# CAN_BUS.net
KiCad netlist of a schematic drawn in Altium Designer
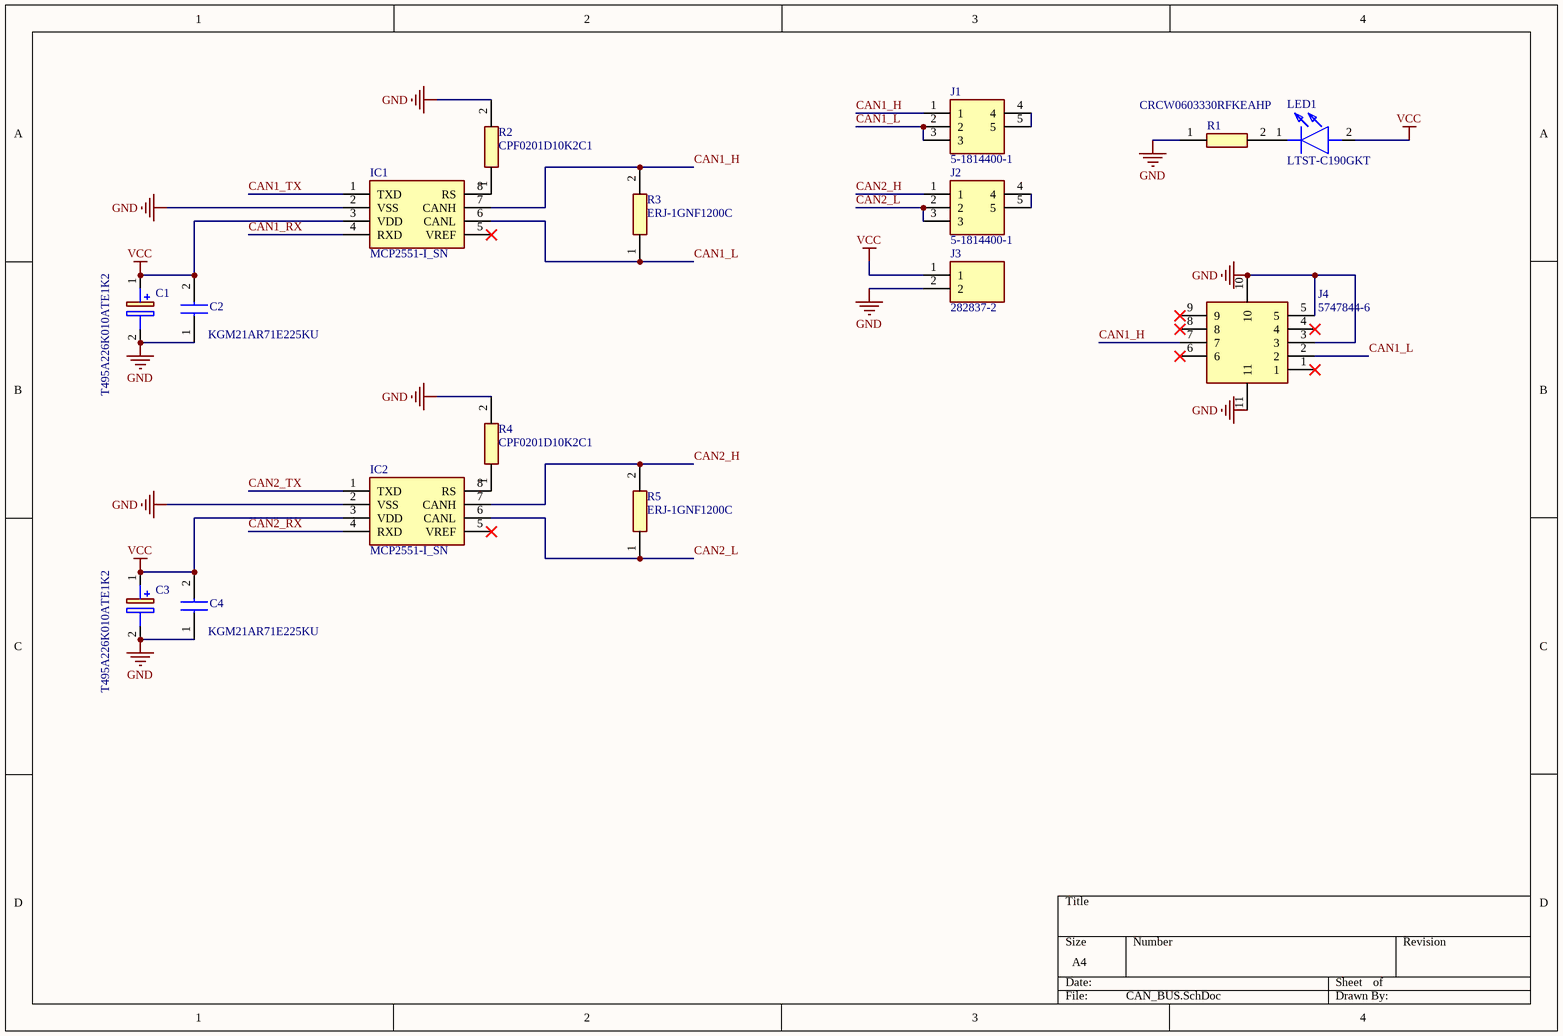
[diagram p0: CAN_BUS.SchDoc]

(export (version "E")
  (design (tool "Eeschema 10.0.6"))
  (components
    (comp (ref "C1")
      (value "T495A226K010ATE1K2")
      (footprint "CAN_BUS:T495A")
      (description "Capacitor Polarised")
      (fields (field (name "MOUSER PART NUMBER") "80-T495A226K10ATE1K2"))
      (libsource (lib "*") (part "T495A226K010ATE1K2"))
    )
    (comp (ref "C2")
      (value "KGM21AR71E225KU")
      (footprint "CAN_BUS:CAPC2012X135N")
      (description "Capacitor")
      (fields (field (name "MOUSER PART NUMBER") "581-KGM21AR71E225KU"))
      (libsource (lib "*") (part "KGM21AR71E225KU"))
    )
    (comp (ref "C3")
      (value "T495A226K010ATE1K2")
      (footprint "CAN_BUS:T495A")
      (description "Capacitor Polarised")
      (fields (field (name "MOUSER PART NUMBER") "80-T495A226K10ATE1K2"))
      (libsource (lib "*") (part "T495A226K010ATE1K2"))
    )
    (comp (ref "C4")
      (value "KGM21AR71E225KU")
      (footprint "CAN_BUS:CAPC2012X135N")
      (description "Capacitor")
      (fields (field (name "MOUSER PART NUMBER") "581-KGM21AR71E225KU"))
      (libsource (lib "*") (part "KGM21AR71E225KU"))
    )
    (comp (ref "IC1")
      (value "MCP2551-I_SN")
      (footprint "OptoIso:SOIC127P600X175-8N")
      (description "Integrated Circuit")
      (fields
        (field (name "MANUFACTURER_PART_NUMBER") "MCP2551-I/SN")
        (field (name "MOUSER PART NUMBER") "579-MCP2551-I/SN")
      )
      (libsource (lib "*") (part "MCP2551-I_SN"))
    )
    (comp (ref "IC2")
      (value "MCP2551-I_SN")
      (footprint "OptoIso:SOIC127P600X175-8N")
      (description "Integrated Circuit")
      (fields
        (field (name "MANUFACTURER_PART_NUMBER") "MCP2551-I/SN")
        (field (name "MOUSER PART NUMBER") "579-MCP2551-I/SN")
      )
      (libsource (lib "*") (part "MCP2551-I_SN"))
    )
    (comp (ref "J1")
      (value "5-1814400-1")
      (footprint "CAN_BUS:518144001")
      (description "Connector")
      (fields (field (name "MOUSER PART NUMBER") "571-5-1814400-1"))
      (libsource (lib "*") (part "5-1814400-1"))
    )
    (comp (ref "J2")
      (value "5-1814400-1")
      (footprint "CAN_BUS:518144001")
      (description "Connector")
      (fields (field (name "MOUSER PART NUMBER") "571-5-1814400-1"))
      (libsource (lib "*") (part "5-1814400-1"))
    )
    (comp (ref "J3")
      (value "282837-2")
      (footprint "CAN_BUS:2828372")
      (description "Connector")
      (fields (field (name "MOUSER PART NUMBER") "571-2828372"))
      (libsource (lib "*") (part "282837-2"))
    )
    (comp (ref "J4")
      (value "5747844-6")
      (footprint "CAN_BUS:57478446")
      (description "Connector")
      (fields (field (name "MOUSER PART NUMBER") "571-5747844-6"))
      (libsource (lib "*") (part "5747844-6"))
    )
    (comp (ref "LED1")
      (value "LTST-C190GKT")
      (footprint "CAN_BUS:LEDC1608X90N")
      (description "LED")
      (fields (field (name "MOUSER PART NUMBER") "859-LTST-C190GKT"))
      (libsource (lib "*") (part "LTST-C190GKT"))
    )
    (comp (ref "R1")
      (value "CRCW0603330RFKEAHP")
      (footprint "CAN_BUS:CAPC1608X55N")
      (description "Resistor")
      (fields (field (name "MOUSER PART NUMBER") "71-CRCW0603330RFKEAH"))
      (libsource (lib "*") (part "CRCW0603330RFKEAHP"))
    )
    (comp (ref "R2")
      (value "CPF0201D10K2C1")
      (footprint "OptoIso:RESC0603X28N")
      (description "Resistor")
      (libsource (lib "*") (part "CPF0201D10K2C1"))
    )
    (comp (ref "R3")
      (value "ERJ-1GNF1200C")
      (footprint "CAN_BUS:ERJ1GN_(0201)")
      (description "Resistor")
      (fields (field (name "MOUSER PART NUMBER") "667-ERJ-1GNF1200C"))
      (libsource (lib "*") (part "ERJ-1GNF1200C"))
    )
    (comp (ref "R4")
      (value "CPF0201D10K2C1")
      (footprint "OptoIso:RESC0603X28N")
      (description "Resistor")
      (libsource (lib "*") (part "CPF0201D10K2C1"))
    )
    (comp (ref "R5")
      (value "ERJ-1GNF1200C")
      (footprint "CAN_BUS:ERJ1GN_(0201)")
      (description "Resistor")
      (fields (field (name "MOUSER PART NUMBER") "667-ERJ-1GNF1200C"))
      (libsource (lib "*") (part "ERJ-1GNF1200C"))
    )
  )
  (nets
    (net (code "1") (name "/CAN1_H") (class "Default")
      (node (ref "IC1") (pin "7") (pinfunction "CANH_7") (pintype "passive"))
      (node (ref "J1") (pin "1") (pinfunction "1_1") (pintype "passive"))
      (node (ref "J4") (pin "7") (pinfunction "7_7") (pintype "passive"))
      (node (ref "R3") (pin "2") (pinfunction "2_2") (pintype "passive"))
    )
    (net (code "2") (name "/CAN1_L") (class "Default")
      (node (ref "IC1") (pin "6") (pinfunction "CANL_6") (pintype "passive"))
      (node (ref "J1") (pin "2") (pinfunction "2_2") (pintype "passive"))
      (node (ref "J1") (pin "3") (pinfunction "3_3") (pintype "passive"))
      (node (ref "J4") (pin "2") (pinfunction "2_2") (pintype "passive"))
      (node (ref "R3") (pin "1") (pinfunction "1_1") (pintype "passive"))
    )
    (net (code "3") (name "/CAN1_RX") (class "Default")
      (node (ref "IC1") (pin "4") (pinfunction "RXD_4") (pintype "passive"))
    )
    (net (code "4") (name "/CAN1_TX") (class "Default")
      (node (ref "IC1") (pin "1") (pinfunction "TXD_1") (pintype "passive"))
    )
    (net (code "5") (name "/CAN2_H") (class "Default")
      (node (ref "IC2") (pin "7") (pinfunction "CANH_7") (pintype "passive"))
      (node (ref "J2") (pin "1") (pinfunction "1_1") (pintype "passive"))
      (node (ref "R5") (pin "2") (pinfunction "2_2") (pintype "passive"))
    )
    (net (code "6") (name "/CAN2_L") (class "Default")
      (node (ref "IC2") (pin "6") (pinfunction "CANL_6") (pintype "passive"))
      (node (ref "J2") (pin "2") (pinfunction "2_2") (pintype "passive"))
      (node (ref "J2") (pin "3") (pinfunction "3_3") (pintype "passive"))
      (node (ref "R5") (pin "1") (pinfunction "1_1") (pintype "passive"))
    )
    (net (code "7") (name "/CAN2_RX") (class "Default")
      (node (ref "IC2") (pin "4") (pinfunction "RXD_4") (pintype "passive"))
    )
    (net (code "8") (name "/CAN2_TX") (class "Default")
      (node (ref "IC2") (pin "1") (pinfunction "TXD_1") (pintype "passive"))
    )
    (net (code "9") (name "GND") (class "Default")
      (node (ref "C1") (pin "2") (pinfunction "-_2") (pintype "passive"))
      (node (ref "C2") (pin "1") (pinfunction "1_1") (pintype "passive"))
      (node (ref "C3") (pin "2") (pinfunction "-_2") (pintype "passive"))
      (node (ref "C4") (pin "1") (pinfunction "1_1") (pintype "passive"))
      (node (ref "IC1") (pin "2") (pinfunction "VSS_2") (pintype "passive"))
      (node (ref "IC2") (pin "2") (pinfunction "VSS_2") (pintype "passive"))
      (node (ref "J3") (pin "2") (pinfunction "2_2") (pintype "passive"))
      (node (ref "J4") (pin "10") (pinfunction "10_10") (pintype "passive"))
      (node (ref "J4") (pin "11") (pinfunction "11_11") (pintype "passive"))
      (node (ref "J4") (pin "3") (pinfunction "3_3") (pintype "passive"))
      (node (ref "J4") (pin "5") (pinfunction "5_5") (pintype "passive"))
      (node (ref "R1") (pin "1") (pinfunction "1_1") (pintype "passive"))
      (node (ref "R2") (pin "2") (pinfunction "2_2") (pintype "passive"))
      (node (ref "R4") (pin "2") (pinfunction "2_2") (pintype "passive"))
    )
    (net (code "10") (name "Net-(IC1-RS)") (class "Default")
      (node (ref "IC1") (pin "8") (pinfunction "RS_8") (pintype "passive"))
      (node (ref "R2") (pin "1") (pinfunction "1_1") (pintype "passive"))
    )
    (net (code "11") (name "Net-(IC2-RS)") (class "Default")
      (node (ref "IC2") (pin "8") (pinfunction "RS_8") (pintype "passive"))
      (node (ref "R4") (pin "1") (pinfunction "1_1") (pintype "passive"))
    )
    (net (code "12") (name "Net-(J1-Pad4)") (class "Default")
      (node (ref "J1") (pin "4") (pinfunction "4_4") (pintype "passive"))
      (node (ref "J1") (pin "5") (pinfunction "5_5") (pintype "passive"))
    )
    (net (code "13") (name "Net-(J2-Pad4)") (class "Default")
      (node (ref "J2") (pin "4") (pinfunction "4_4") (pintype "passive"))
      (node (ref "J2") (pin "5") (pinfunction "5_5") (pintype "passive"))
    )
    (net (code "14") (name "Net-(LED1-K)") (class "Default")
      (node (ref "LED1") (pin "1") (pinfunction "K_1") (pintype "passive"))
      (node (ref "R1") (pin "2") (pinfunction "2_2") (pintype "passive"))
    )
    (net (code "15") (name "VCC") (class "Default")
      (node (ref "C1") (pin "1") (pinfunction "+_1") (pintype "passive"))
      (node (ref "C2") (pin "2") (pinfunction "2_2") (pintype "passive"))
      (node (ref "C3") (pin "1") (pinfunction "+_1") (pintype "passive"))
      (node (ref "C4") (pin "2") (pinfunction "2_2") (pintype "passive"))
      (node (ref "IC1") (pin "3") (pinfunction "VDD_3") (pintype "passive"))
      (node (ref "IC2") (pin "3") (pinfunction "VDD_3") (pintype "passive"))
      (node (ref "J3") (pin "1") (pinfunction "1_1") (pintype "passive"))
      (node (ref "LED1") (pin "2") (pinfunction "A_2") (pintype "passive"))
    )
    (net (code "16") (name "unconnected-(IC1-VREF-Pad5)") (class "Default")
      (node (ref "IC1") (pin "5") (pinfunction "VREF_5") (pintype "passive+no_connect"))
    )
    (net (code "17") (name "unconnected-(IC2-VREF-Pad5)") (class "Default")
      (node (ref "IC2") (pin "5") (pinfunction "VREF_5") (pintype "passive+no_connect"))
    )
    (net (code "18") (name "unconnected-(J4-Pad1)") (class "Default")
      (node (ref "J4") (pin "1") (pinfunction "1_1") (pintype "passive+no_connect"))
    )
    (net (code "19") (name "unconnected-(J4-Pad4)") (class "Default")
      (node (ref "J4") (pin "4") (pinfunction "4_4") (pintype "passive+no_connect"))
    )
    (net (code "20") (name "unconnected-(J4-Pad6)") (class "Default")
      (node (ref "J4") (pin "6") (pinfunction "6_6") (pintype "passive+no_connect"))
    )
    (net (code "21") (name "unconnected-(J4-Pad8)") (class "Default")
      (node (ref "J4") (pin "8") (pinfunction "8_8") (pintype "passive+no_connect"))
    )
    (net (code "22") (name "unconnected-(J4-Pad9)") (class "Default")
      (node (ref "J4") (pin "9") (pinfunction "9_9") (pintype "passive+no_connect"))
    )
  )
)
